# annoyatron_revA.net
KiCad netlist of a schematic drawn in EAGLE
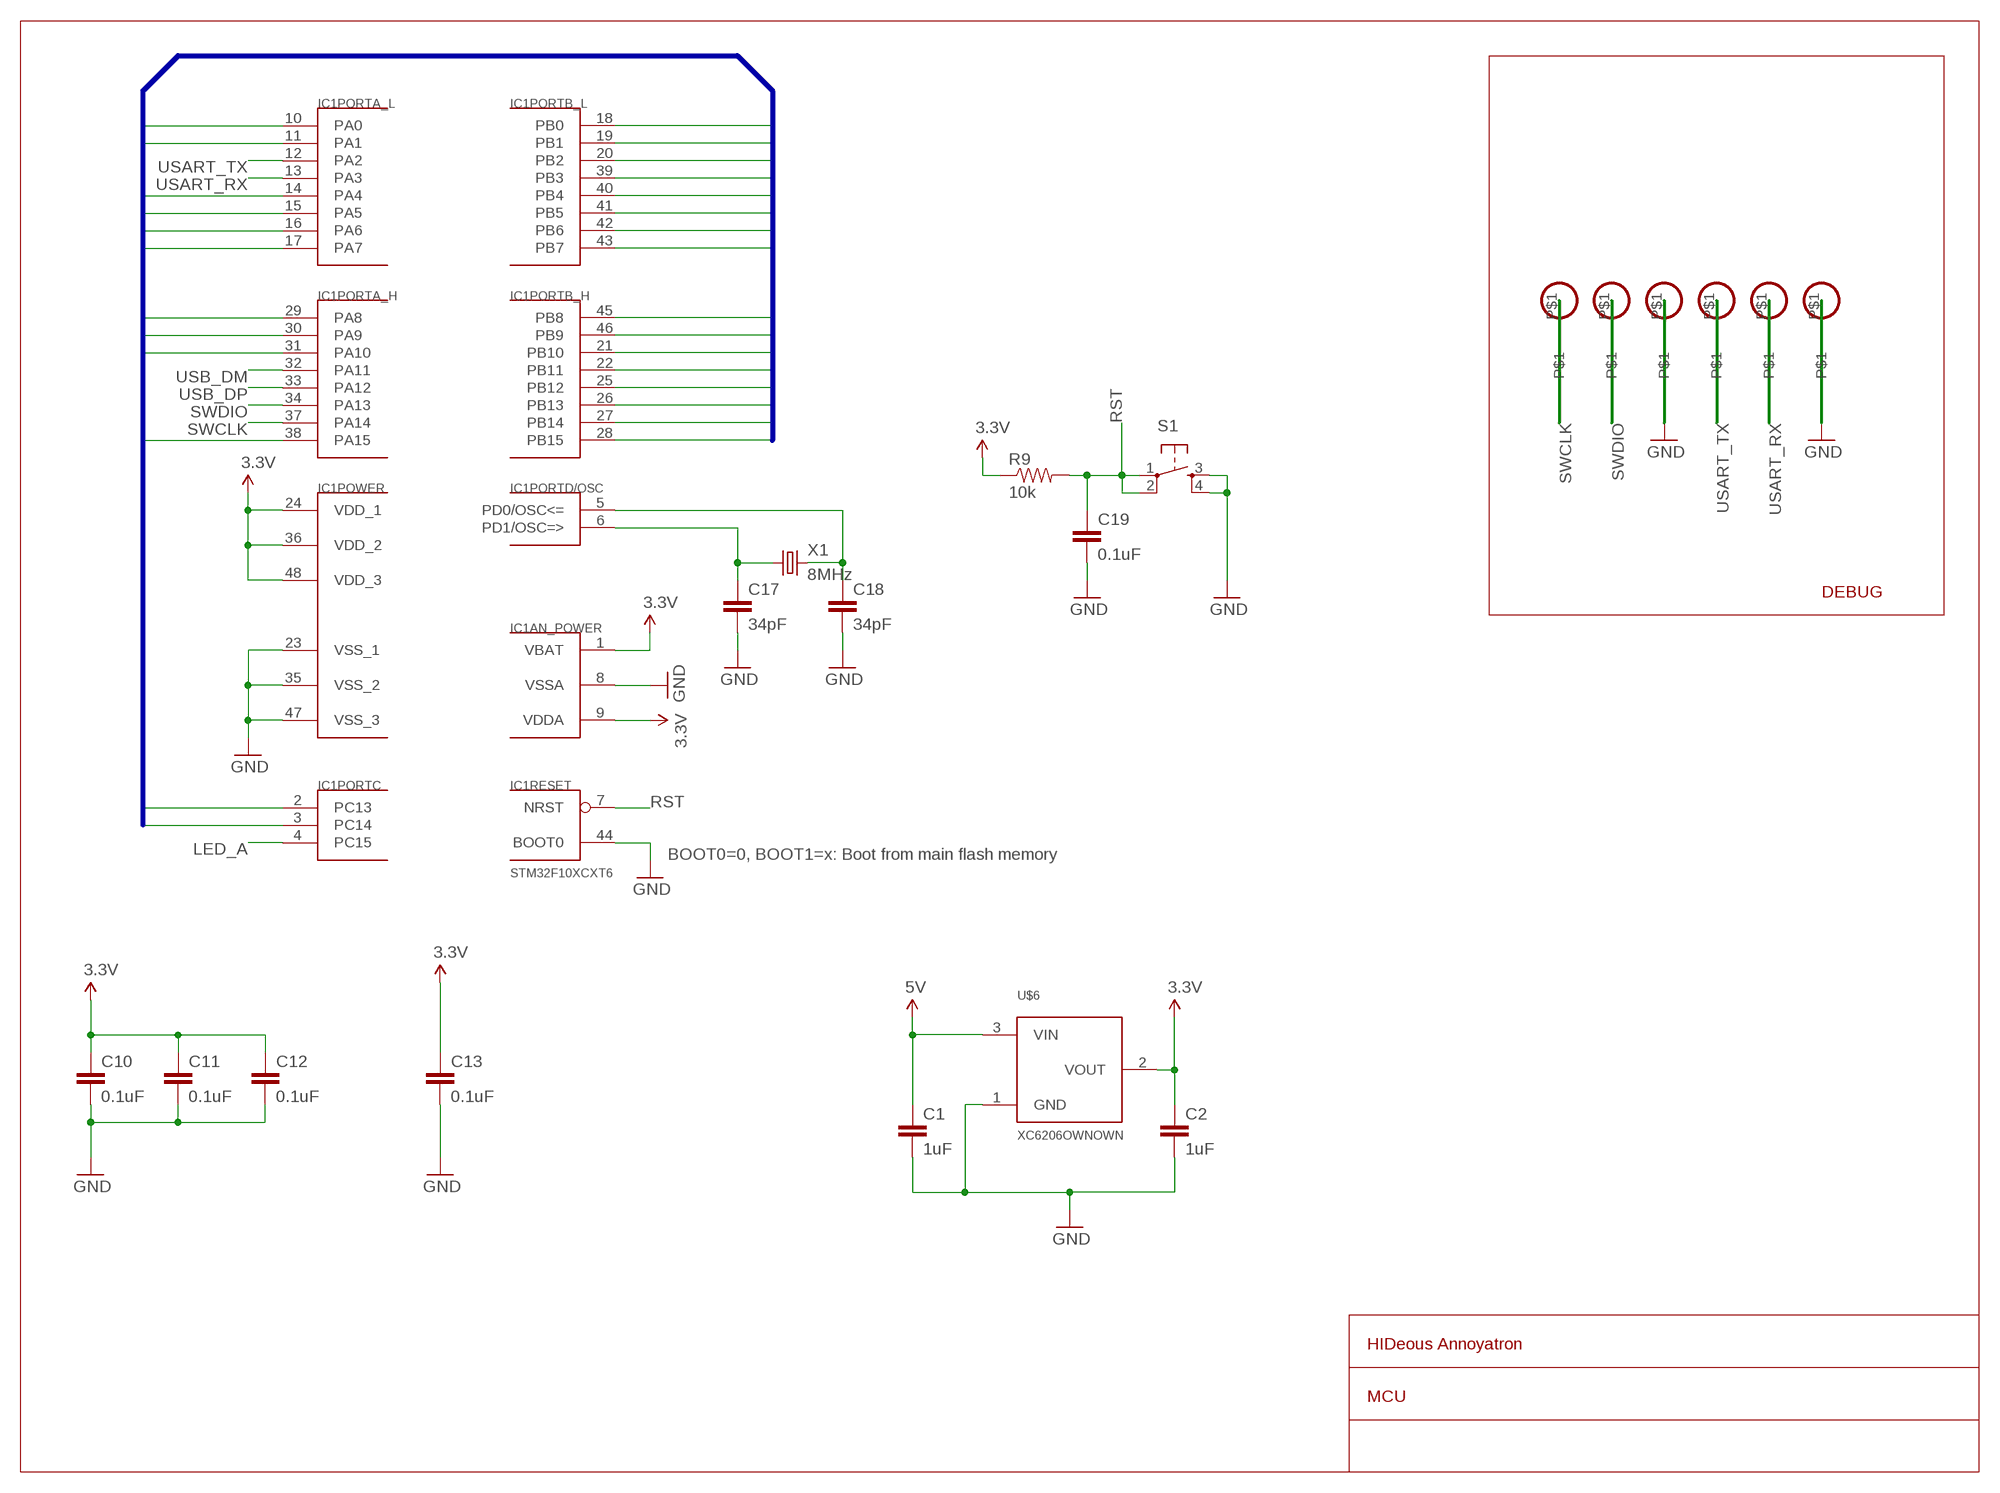
[diagram p0: schematic, sheet 1]
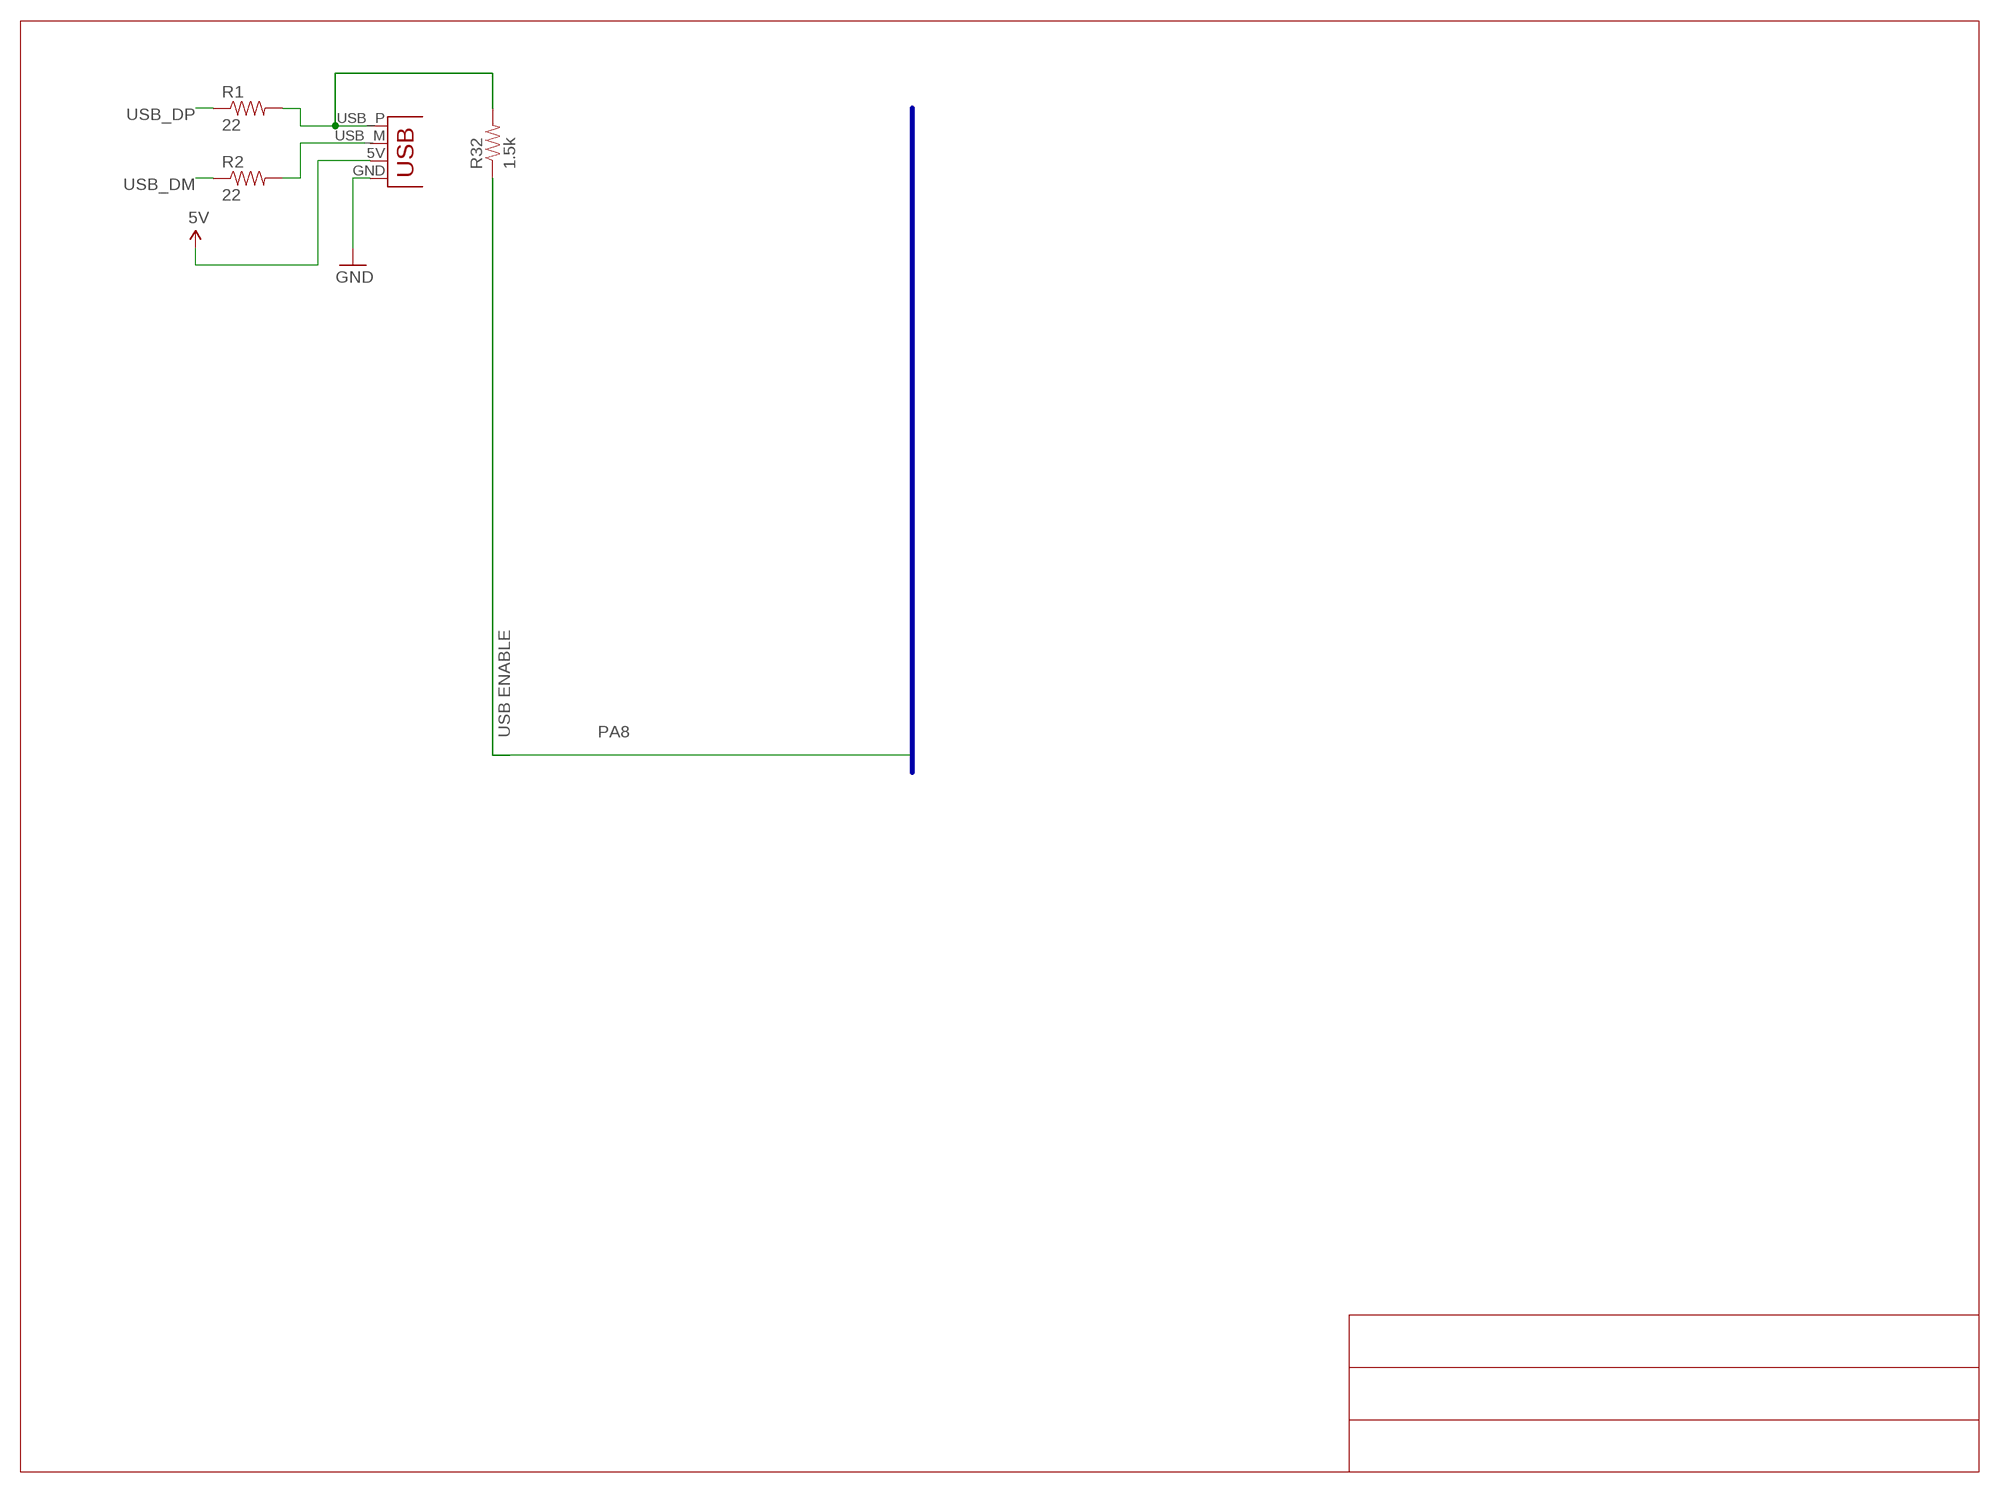
[diagram p1: schematic, sheet 2]

(export (version "E")
  (design (tool "Eeschema 10.0.6"))
  (components
    (comp (ref "JP1")
      (value "USBPCB")
      (footprint "eagle-import:USB-A-PCB")
      (libsource (lib "eagle-import") (part "USBPCB"))
    )
    (comp (ref "R1")
      (value "22")
      (footprint "eagle-import:C0402")
      (libsource (lib "eagle-import") (part "RESISTOR0402"))
    )
    (comp (ref "R2")
      (value "22")
      (footprint "eagle-import:C0402")
      (libsource (lib "eagle-import") (part "RESISTOR0402"))
    )
    (comp (ref "R32")
      (value "1.5k")
      (footprint "eagle-import:C0402")
      (libsource (lib "eagle-import") (part "RESISTOR0402"))
    )
    (comp (ref "C1")
      (value "1uF")
      (footprint "eagle-import:0805_GEN")
      (libsource (lib "eagle-import") (part "CAP0805"))
    )
    (comp (ref "C2")
      (value "1uF")
      (footprint "eagle-import:0805_GEN")
      (libsource (lib "eagle-import") (part "CAP0805"))
    )
    (comp (ref "C10")
      (value "0.1uF")
      (footprint "eagle-import:C0402")
      (libsource (lib "eagle-import") (part "CAP0402"))
    )
    (comp (ref "C11")
      (value "0.1uF")
      (footprint "eagle-import:C0402")
      (libsource (lib "eagle-import") (part "CAP0402"))
    )
    (comp (ref "C12")
      (value "0.1uF")
      (footprint "eagle-import:C0402")
      (libsource (lib "eagle-import") (part "CAP0402"))
    )
    (comp (ref "C13")
      (value "0.1uF")
      (footprint "eagle-import:C0402")
      (libsource (lib "eagle-import") (part "CAP0402"))
    )
    (comp (ref "C17")
      (value "34pF")
      (footprint "eagle-import:C0402")
      (libsource (lib "eagle-import") (part "CAP0402"))
    )
    (comp (ref "C18")
      (value "34pF")
      (footprint "eagle-import:C0402")
      (libsource (lib "eagle-import") (part "CAP0402"))
    )
    (comp (ref "C19")
      (value "0.1uF")
      (footprint "eagle-import:C0402")
      (libsource (lib "eagle-import") (part "CAP0402"))
    )
    (comp (ref "IC1")
      (value "STM32F10XCXT6")
      (footprint "eagle-import:TQFP48")
      (libsource (lib "eagle-import") (part "STM32F10XCXT6"))
    )
    (comp (ref "R9")
      (value "10k")
      (footprint "eagle-import:C0402")
      (libsource (lib "eagle-import") (part "RESISTOR0402"))
    )
    (comp (ref "S1")
      (value "TAC_SWITCHSMD")
      (footprint "eagle-import:TACTILE_SWITCH_SMD")
      (libsource (lib "eagle-import") (part "TAC_SWITCHSMD"))
    )
    (comp (ref "U$2")
      (value "PADOWN")
      (footprint "eagle-import:PAD2MM")
      (libsource (lib "eagle-import") (part "PADOWN"))
    )
    (comp (ref "U$3")
      (value "PADOWN")
      (footprint "eagle-import:PAD2MM")
      (libsource (lib "eagle-import") (part "PADOWN"))
    )
    (comp (ref "U$4")
      (value "PADOWN")
      (footprint "eagle-import:PAD2MM")
      (libsource (lib "eagle-import") (part "PADOWN"))
    )
    (comp (ref "U$5")
      (value "PADOWN")
      (footprint "eagle-import:PAD2MM")
      (libsource (lib "eagle-import") (part "PADOWN"))
    )
    (comp (ref "U$6")
      (value "XC6206OWNOWN")
      (footprint "eagle-import:SOT23")
      (libsource (lib "eagle-import") (part "XC6206OWNOWN"))
    )
    (comp (ref "U$9")
      (value "PADOWN")
      (footprint "eagle-import:PAD2MM")
      (libsource (lib "eagle-import") (part "PADOWN"))
    )
    (comp (ref "U$10")
      (value "PADOWN")
      (footprint "eagle-import:PAD2MM")
      (libsource (lib "eagle-import") (part "PADOWN"))
    )
    (comp (ref "X1")
      (value "8MHz")
      (footprint "eagle-import:CRYSTAL_SMD_5X3.2_7A")
      (libsource (lib "eagle-import") (part "CRYSTAL5X3.2_7AOWN"))
    )
  )
  (nets
    (net (code "1") (name "3.3V") (class "Default")
      (node (ref "C10") (pin "1") (pinfunction "1_1") (pintype "passive"))
      (node (ref "C11") (pin "1") (pinfunction "1_1") (pintype "passive"))
      (node (ref "C12") (pin "1") (pinfunction "1_1") (pintype "passive"))
      (node (ref "C13") (pin "1") (pinfunction "1_1") (pintype "passive"))
      (node (ref "C2") (pin "1") (pinfunction "1_1") (pintype "passive"))
      (node (ref "IC1") (pin "1") (pinfunction "VBAT_1") (pintype "power_in"))
      (node (ref "IC1") (pin "24") (pinfunction "VDD_1_24") (pintype "power_in"))
      (node (ref "IC1") (pin "36") (pinfunction "VDD_2_36") (pintype "power_in"))
      (node (ref "IC1") (pin "48") (pinfunction "VDD_3_48") (pintype "power_in"))
      (node (ref "IC1") (pin "9") (pinfunction "VDDA_9") (pintype "power_in"))
      (node (ref "R9") (pin "1") (pinfunction "1_1") (pintype "passive"))
      (node (ref "U$6") (pin "2") (pinfunction "VOUT_2") (pintype "power_in"))
    )
    (net (code "2") (name "5V") (class "Default")
      (node (ref "C1") (pin "1") (pinfunction "1_1") (pintype "passive"))
      (node (ref "JP1") (pin "5V") (pinfunction "VBUS_5V") (pintype "bidirectional"))
      (node (ref "U$6") (pin "3") (pinfunction "VIN_3") (pintype "power_in"))
    )
    (net (code "3") (name "GND") (class "Default")
      (node (ref "C1") (pin "2") (pinfunction "2_2") (pintype "passive"))
      (node (ref "C10") (pin "2") (pinfunction "2_2") (pintype "passive"))
      (node (ref "C11") (pin "2") (pinfunction "2_2") (pintype "passive"))
      (node (ref "C12") (pin "2") (pinfunction "2_2") (pintype "passive"))
      (node (ref "C13") (pin "2") (pinfunction "2_2") (pintype "passive"))
      (node (ref "C17") (pin "2") (pinfunction "2_2") (pintype "passive"))
      (node (ref "C18") (pin "2") (pinfunction "2_2") (pintype "passive"))
      (node (ref "C19") (pin "2") (pinfunction "2_2") (pintype "passive"))
      (node (ref "C2") (pin "2") (pinfunction "2_2") (pintype "passive"))
      (node (ref "IC1") (pin "23") (pinfunction "VSS_1_23") (pintype "power_in"))
      (node (ref "IC1") (pin "35") (pinfunction "VSS_2_35") (pintype "power_in"))
      (node (ref "IC1") (pin "44") (pinfunction "BOOT0_44") (pintype "input"))
      (node (ref "IC1") (pin "47") (pinfunction "VSS_3_47") (pintype "power_in"))
      (node (ref "IC1") (pin "8") (pinfunction "VSSA_8") (pintype "power_in"))
      (node (ref "JP1") (pin "GND") (pinfunction "GND_GND") (pintype "bidirectional"))
      (node (ref "S1") (pin "3") (pinfunction "3_3") (pintype "passive"))
      (node (ref "S1") (pin "4") (pinfunction "4_4") (pintype "passive"))
      (node (ref "U$10") (pin "P$1") (pinfunction "P$1_P$1") (pintype "bidirectional"))
      (node (ref "U$4") (pin "P$1") (pinfunction "P$1_P$1") (pintype "bidirectional"))
      (node (ref "U$6") (pin "1") (pinfunction "GND_1") (pintype "power_in"))
    )
    (net (code "4") (name "LED_A") (class "Default")
      (node (ref "IC1") (pin "4") (pinfunction "PC15_4") (pintype "bidirectional"))
    )
    (net (code "5") (name "Net-(IC1G-PD0{slash}OSC<=)") (class "Default")
      (node (ref "C18") (pin "1") (pinfunction "1_1") (pintype "passive"))
      (node (ref "IC1") (pin "5") (pinfunction "PD0/OSC<=_5") (pintype "bidirectional"))
      (node (ref "X1") (pin "P$2") (pinfunction "2_P$2") (pintype "passive"))
    )
    (net (code "6") (name "Net-(IC1G-PD1{slash}OSC=>)") (class "Default")
      (node (ref "C17") (pin "1") (pinfunction "1_1") (pintype "passive"))
      (node (ref "IC1") (pin "6") (pinfunction "PD1/OSC=>_6") (pintype "bidirectional"))
      (node (ref "X1") (pin "P$1") (pinfunction "1_P$1") (pintype "passive"))
    )
    (net (code "7") (name "Net-(JP1-D+)") (class "Default")
      (node (ref "JP1") (pin "USB_P") (pinfunction "D+_USB_P") (pintype "bidirectional"))
      (node (ref "R1") (pin "2") (pinfunction "2_2") (pintype "passive"))
      (node (ref "R32") (pin "2") (pinfunction "2_2") (pintype "passive"))
    )
    (net (code "8") (name "Net-(JP1-D-)") (class "Default")
      (node (ref "JP1") (pin "USB_M") (pinfunction "D-_USB_M") (pintype "bidirectional"))
      (node (ref "R2") (pin "2") (pinfunction "2_2") (pintype "passive"))
    )
    (net (code "9") (name "PA8") (class "Default")
      (node (ref "IC1") (pin "29") (pinfunction "PA8_29") (pintype "bidirectional"))
      (node (ref "R32") (pin "1") (pinfunction "1_1") (pintype "passive"))
    )
    (net (code "10") (name "RST") (class "Default")
      (node (ref "C19") (pin "1") (pinfunction "1_1") (pintype "passive"))
      (node (ref "IC1") (pin "7") (pinfunction "NRST_7") (pintype "input"))
      (node (ref "R9") (pin "2") (pinfunction "2_2") (pintype "passive"))
      (node (ref "S1") (pin "1") (pinfunction "1_1") (pintype "passive"))
      (node (ref "S1") (pin "2") (pinfunction "2_2") (pintype "passive"))
    )
    (net (code "11") (name "SWCLK") (class "Default")
      (node (ref "IC1") (pin "37") (pinfunction "PA14_37") (pintype "bidirectional"))
      (node (ref "U$2") (pin "P$1") (pinfunction "P$1_P$1") (pintype "bidirectional"))
    )
    (net (code "12") (name "SWDIO") (class "Default")
      (node (ref "IC1") (pin "34") (pinfunction "PA13_34") (pintype "bidirectional"))
      (node (ref "U$3") (pin "P$1") (pinfunction "P$1_P$1") (pintype "bidirectional"))
    )
    (net (code "13") (name "USART_RX") (class "Default")
      (node (ref "IC1") (pin "13") (pinfunction "PA3_13") (pintype "bidirectional"))
      (node (ref "U$9") (pin "P$1") (pinfunction "P$1_P$1") (pintype "bidirectional"))
    )
    (net (code "14") (name "USART_TX") (class "Default")
      (node (ref "IC1") (pin "12") (pinfunction "PA2_12") (pintype "bidirectional"))
      (node (ref "U$5") (pin "P$1") (pinfunction "P$1_P$1") (pintype "bidirectional"))
    )
    (net (code "15") (name "USB_DM") (class "Default")
      (node (ref "IC1") (pin "32") (pinfunction "PA11_32") (pintype "bidirectional"))
      (node (ref "R2") (pin "1") (pinfunction "1_1") (pintype "passive"))
    )
    (net (code "16") (name "USB_DP") (class "Default")
      (node (ref "IC1") (pin "33") (pinfunction "PA12_33") (pintype "bidirectional"))
      (node (ref "R1") (pin "1") (pinfunction "1_1") (pintype "passive"))
    )
    (net (code "17") (name "unconnected-(IC1B-PA9-Pad30)") (class "Default")
      (node (ref "IC1") (pin "30") (pinfunction "PA9_30") (pintype "bidirectional"))
    )
    (net (code "18") (name "unconnected-(IC1B-PA10-Pad31)") (class "Default")
      (node (ref "IC1") (pin "31") (pinfunction "PA10_31") (pintype "bidirectional"))
    )
    (net (code "19") (name "unconnected-(IC1B-PA15-Pad38)") (class "Default")
      (node (ref "IC1") (pin "38") (pinfunction "PA15_38") (pintype "bidirectional"))
    )
    (net (code "20") (name "unconnected-(IC1C-PA0-Pad10)") (class "Default")
      (node (ref "IC1") (pin "10") (pinfunction "PA0_10") (pintype "bidirectional"))
    )
    (net (code "21") (name "unconnected-(IC1C-PA1-Pad11)") (class "Default")
      (node (ref "IC1") (pin "11") (pinfunction "PA1_11") (pintype "bidirectional"))
    )
    (net (code "22") (name "unconnected-(IC1C-PA4-Pad14)") (class "Default")
      (node (ref "IC1") (pin "14") (pinfunction "PA4_14") (pintype "bidirectional"))
    )
    (net (code "23") (name "unconnected-(IC1C-PA5-Pad15)") (class "Default")
      (node (ref "IC1") (pin "15") (pinfunction "PA5_15") (pintype "bidirectional"))
    )
    (net (code "24") (name "unconnected-(IC1C-PA6-Pad16)") (class "Default")
      (node (ref "IC1") (pin "16") (pinfunction "PA6_16") (pintype "bidirectional"))
    )
    (net (code "25") (name "unconnected-(IC1C-PA7-Pad17)") (class "Default")
      (node (ref "IC1") (pin "17") (pinfunction "PA7_17") (pintype "bidirectional"))
    )
    (net (code "26") (name "unconnected-(IC1D-PB8-Pad45)") (class "Default")
      (node (ref "IC1") (pin "45") (pinfunction "PB8_45") (pintype "bidirectional"))
    )
    (net (code "27") (name "unconnected-(IC1D-PB9-Pad46)") (class "Default")
      (node (ref "IC1") (pin "46") (pinfunction "PB9_46") (pintype "bidirectional"))
    )
    (net (code "28") (name "unconnected-(IC1D-PB10-Pad21)") (class "Default")
      (node (ref "IC1") (pin "21") (pinfunction "PB10_21") (pintype "bidirectional"))
    )
    (net (code "29") (name "unconnected-(IC1D-PB11-Pad22)") (class "Default")
      (node (ref "IC1") (pin "22") (pinfunction "PB11_22") (pintype "bidirectional"))
    )
    (net (code "30") (name "unconnected-(IC1D-PB12-Pad25)") (class "Default")
      (node (ref "IC1") (pin "25") (pinfunction "PB12_25") (pintype "bidirectional"))
    )
    (net (code "31") (name "unconnected-(IC1D-PB13-Pad26)") (class "Default")
      (node (ref "IC1") (pin "26") (pinfunction "PB13_26") (pintype "bidirectional"))
    )
    (net (code "32") (name "unconnected-(IC1D-PB14-Pad27)") (class "Default")
      (node (ref "IC1") (pin "27") (pinfunction "PB14_27") (pintype "bidirectional"))
    )
    (net (code "33") (name "unconnected-(IC1D-PB15-Pad28)") (class "Default")
      (node (ref "IC1") (pin "28") (pinfunction "PB15_28") (pintype "bidirectional"))
    )
    (net (code "34") (name "unconnected-(IC1E-PB0-Pad18)") (class "Default")
      (node (ref "IC1") (pin "18") (pinfunction "PB0_18") (pintype "bidirectional"))
    )
    (net (code "35") (name "unconnected-(IC1E-PB1-Pad19)") (class "Default")
      (node (ref "IC1") (pin "19") (pinfunction "PB1_19") (pintype "bidirectional"))
    )
    (net (code "36") (name "unconnected-(IC1E-PB2-Pad20)") (class "Default")
      (node (ref "IC1") (pin "20") (pinfunction "PB2_20") (pintype "bidirectional"))
    )
    (net (code "37") (name "unconnected-(IC1E-PB3-Pad39)") (class "Default")
      (node (ref "IC1") (pin "39") (pinfunction "PB3_39") (pintype "bidirectional"))
    )
    (net (code "38") (name "unconnected-(IC1E-PB4-Pad40)") (class "Default")
      (node (ref "IC1") (pin "40") (pinfunction "PB4_40") (pintype "bidirectional"))
    )
    (net (code "39") (name "unconnected-(IC1E-PB5-Pad41)") (class "Default")
      (node (ref "IC1") (pin "41") (pinfunction "PB5_41") (pintype "bidirectional"))
    )
    (net (code "40") (name "unconnected-(IC1E-PB6-Pad42)") (class "Default")
      (node (ref "IC1") (pin "42") (pinfunction "PB6_42") (pintype "bidirectional"))
    )
    (net (code "41") (name "unconnected-(IC1E-PB7-Pad43)") (class "Default")
      (node (ref "IC1") (pin "43") (pinfunction "PB7_43") (pintype "bidirectional"))
    )
    (net (code "42") (name "unconnected-(IC1F-PC13-Pad2)") (class "Default")
      (node (ref "IC1") (pin "2") (pinfunction "PC13_2") (pintype "bidirectional"))
    )
    (net (code "43") (name "unconnected-(IC1F-PC14-Pad3)") (class "Default")
      (node (ref "IC1") (pin "3") (pinfunction "PC14_3") (pintype "bidirectional"))
    )
  )
)
